# Main.net
KiCad netlist of a schematic drawn in Altium Designer
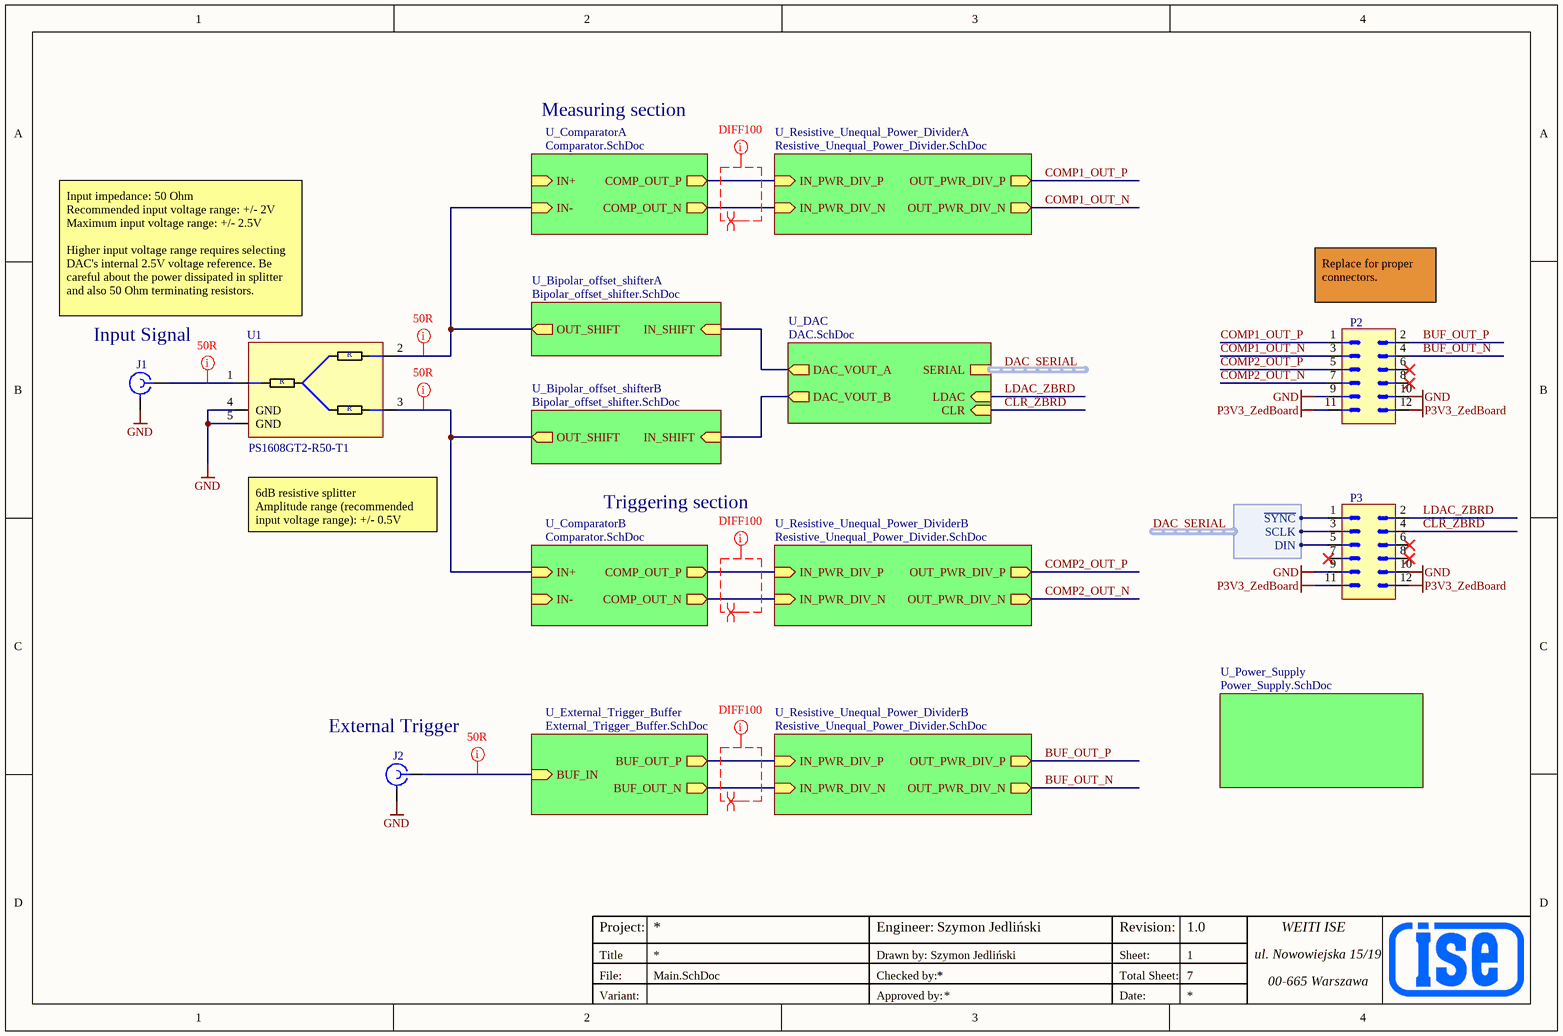
[diagram p0: Main.SchDoc]

(export (version "E")
  (design (tool "Eeschema 10.0.6"))
  (components
    (comp (ref "J1")
      (value "CONSMA020.062-G")
      (description "Coaxial Connectors SMA, Edge Mount, Female Receptacle, 0.062\" PCB Mount, Gold")
      (libsource (lib "Connectors") (part "Coax_1Female_1Shield"))
    )
    (comp (ref "J2")
      (value "CONSMA020.062-G")
      (description "Coaxial Connectors SMA, Edge Mount, Female Receptacle, 0.062\" PCB Mount, Gold")
      (libsource (lib "Connectors") (part "Coax_1Female_1Shield"))
    )
    (comp (ref "P2")
      (value "DF11-12DP-2DSA")
      (footprint "DF11-12DP-2DSA")
      (description "Socket wire-board, male, Pitch 2mm, PIN: 12")
      (libsource (lib "Connectors") (part "Header 6x2"))
    )
    (comp (ref "P3")
      (value "DF11-12DP-2DSA")
      (footprint "DF11-12DP-2DSA")
      (description "Socket wire-board, male, Pitch 2mm, PIN: 12")
      (libsource (lib "Connectors") (part "Header 6x2"))
    )
    (comp (ref "U1")
      (value "PS1608GT2-R50-T1")
      (description "Signal Conditioning 50 ohm 2 terminal Power Splitter")
      (libsource (lib "Resistors") (part "PSXXXXGT2-R50"))
    )
  )
  (nets
    (net (code "3") (name "/BUF_IN") (class "Default")
      (node (ref "J2") (pin "1") (pinfunction "1_1") (pintype "passive"))
    )
    (net (code "4") (name "/BUF_OUT_N") (class "Default")
      (node (ref "P2") (pin "4") (pinfunction "4_4") (pintype "passive"))
    )
    (net (code "6") (name "/BUF_OUT_P") (class "Default")
      (node (ref "P2") (pin "2") (pinfunction "2_2") (pintype "passive"))
    )
    (net (code "8") (name "/CLR_ZBRD") (class "Default")
      (node (ref "P3") (pin "4") (pinfunction "4_4") (pintype "passive"))
    )
    (net (code "9") (name "/COMP1_OUT_N") (class "Default")
      (node (ref "P2") (pin "3") (pinfunction "3_3") (pintype "passive"))
    )
    (net (code "10") (name "/COMP1_OUT_P") (class "Default")
      (node (ref "P2") (pin "1") (pinfunction "1_1") (pintype "passive"))
    )
    (net (code "11") (name "/COMP2_OUT_N") (class "Default")
      (node (ref "P2") (pin "7") (pinfunction "7_7") (pintype "passive"))
    )
    (net (code "12") (name "/COMP2_OUT_P") (class "Default")
      (node (ref "P2") (pin "5") (pinfunction "5_5") (pintype "passive"))
    )
    (net (code "20") (name "/DIN") (class "Default")
      (node (ref "P3") (pin "5") (pinfunction "5_5") (pintype "passive"))
    )
    (net (code "23") (name "/LDAC_ZBRD") (class "Default")
      (node (ref "P3") (pin "2") (pinfunction "2_2") (pintype "passive"))
    )
    (net (code "24") (name "/OUT_SHIFT") (class "Default")
      (node (ref "U1") (pin "2") (pinfunction "2_2") (pintype "passive"))
    )
    (net (code "25") (name "/OUT_SHIFT_1") (class "Default")
      (node (ref "U1") (pin "3") (pinfunction "3_3") (pintype "passive"))
    )
    (net (code "26") (name "/SCLK") (class "Default")
      (node (ref "P3") (pin "3") (pinfunction "3_3") (pintype "passive"))
    )
    (net (code "28") (name "/~{SYNC}") (class "Default")
      (node (ref "P3") (pin "1") (pinfunction "1_1") (pintype "passive"))
    )
    (net (code "29") (name "GND") (class "Default")
      (node (ref "J1") (pin "2") (pinfunction "2_2") (pintype "passive"))
      (node (ref "J2") (pin "2") (pinfunction "2_2") (pintype "passive"))
      (node (ref "P2") (pin "10") (pinfunction "10_10") (pintype "passive"))
      (node (ref "P2") (pin "9") (pinfunction "9_9") (pintype "passive"))
      (node (ref "P3") (pin "10") (pinfunction "10_10") (pintype "passive"))
      (node (ref "P3") (pin "9") (pinfunction "9_9") (pintype "passive"))
      (node (ref "U1") (pin "4") (pinfunction "GND_4") (pintype "passive"))
      (node (ref "U1") (pin "5") (pinfunction "GND_5") (pintype "passive"))
    )
    (net (code "30") (name "Net-(J1-Pad1)") (class "Default")
      (node (ref "J1") (pin "1") (pinfunction "1_1") (pintype "passive"))
      (node (ref "U1") (pin "1") (pinfunction "1_1") (pintype "passive"))
    )
    (net (code "31") (name "P3V3_ZedBoard") (class "Default")
      (node (ref "P2") (pin "11") (pinfunction "11_11") (pintype "passive"))
      (node (ref "P2") (pin "12") (pinfunction "12_12") (pintype "passive"))
      (node (ref "P3") (pin "11") (pinfunction "11_11") (pintype "passive"))
      (node (ref "P3") (pin "12") (pinfunction "12_12") (pintype "passive"))
    )
    (net (code "32") (name "unconnected-(P2-Pad6)") (class "Default")
      (node (ref "P2") (pin "6") (pinfunction "6_6") (pintype "passive+no_connect"))
    )
    (net (code "33") (name "unconnected-(P2-Pad8)") (class "Default")
      (node (ref "P2") (pin "8") (pinfunction "8_8") (pintype "passive+no_connect"))
    )
    (net (code "34") (name "unconnected-(P3-Pad6)") (class "Default")
      (node (ref "P3") (pin "6") (pinfunction "6_6") (pintype "passive+no_connect"))
    )
    (net (code "35") (name "unconnected-(P3-Pad7)") (class "Default")
      (node (ref "P3") (pin "7") (pinfunction "7_7") (pintype "passive+no_connect"))
    )
    (net (code "36") (name "unconnected-(P3-Pad8)") (class "Default")
      (node (ref "P3") (pin "8") (pinfunction "8_8") (pintype "passive+no_connect"))
    )
  )
)
